# ProPrj_usb__2025-12-14-12-09-50.net
KiCad netlist of a schematic drawn in EasyEDA Pro
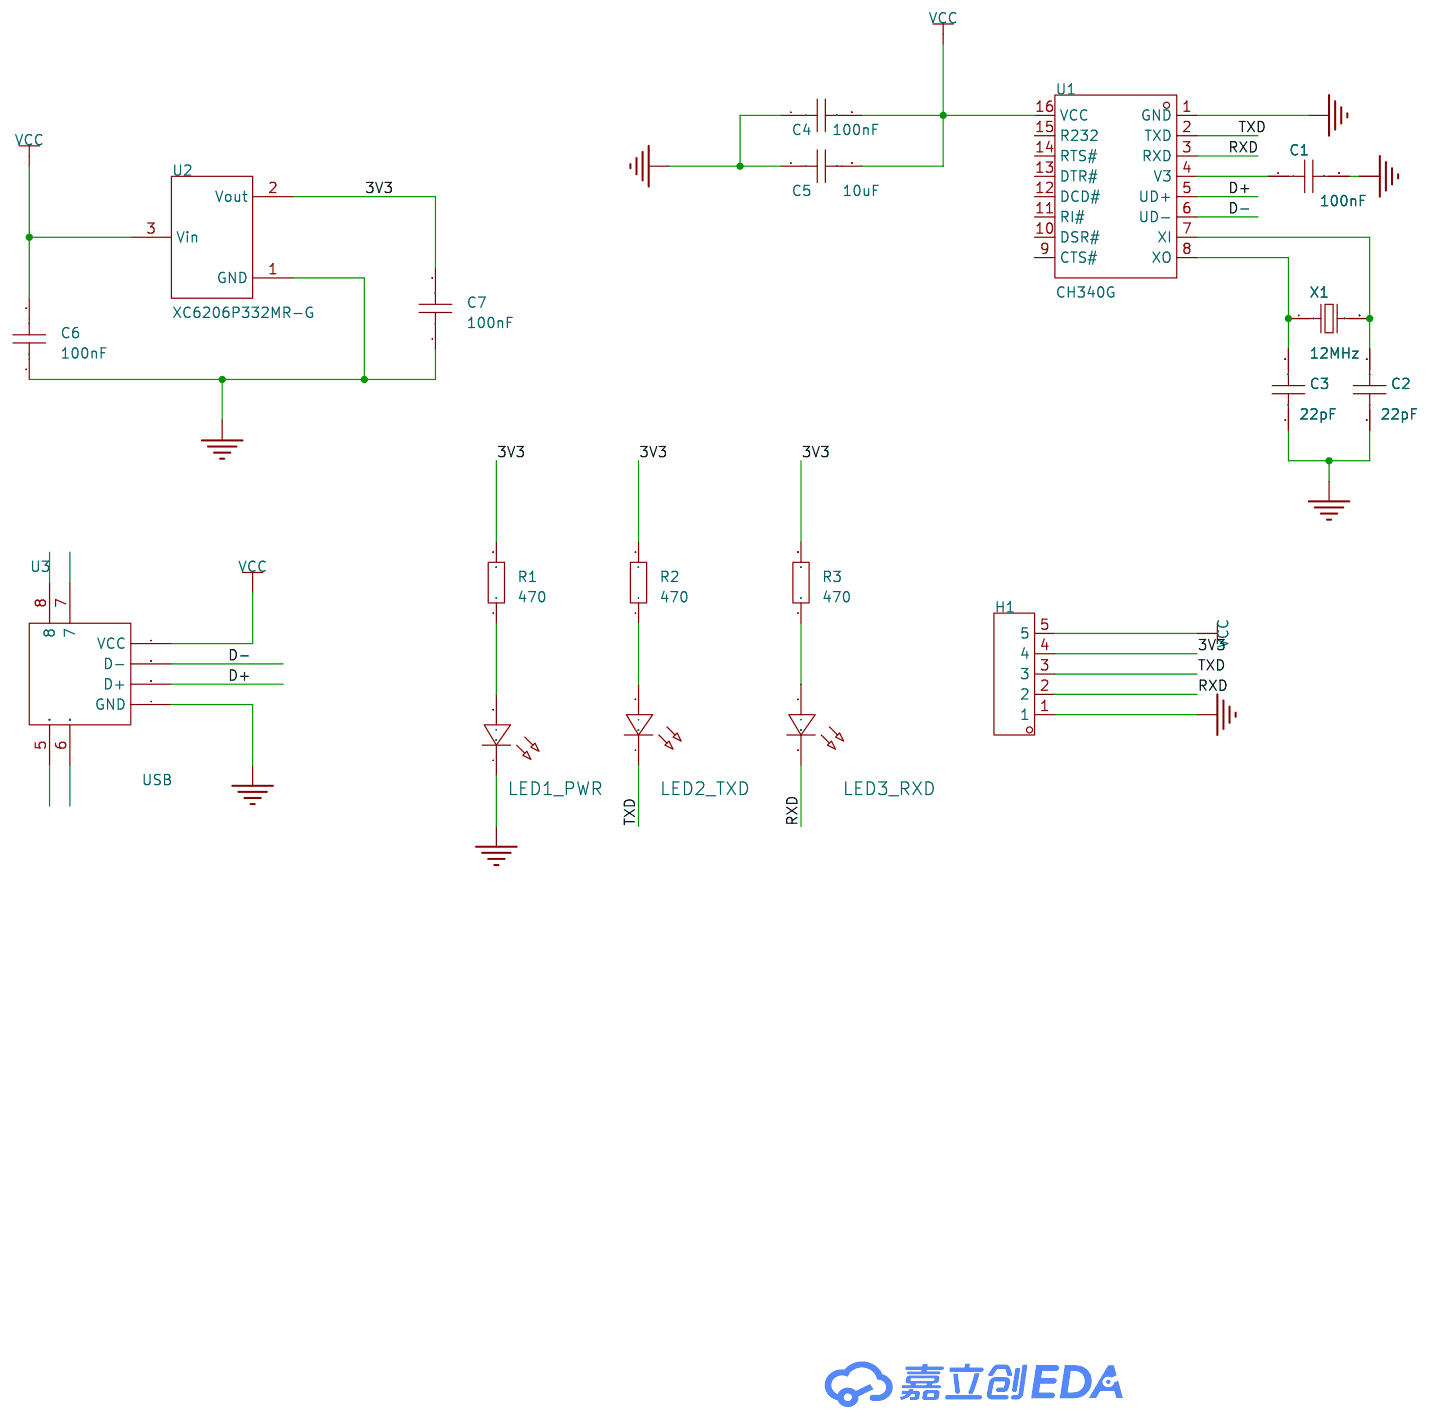
[diagram p0: schematic sheet]

(export (version "E")
  (design (tool "Eeschema 10.0.6"))
  (components
    (comp (ref "C1")
      (value "100nF")
      (footprint "easyedapro:C0603")
      (libsource (lib "easyedapro") (part "Capacitance"))
    )
    (comp (ref "C2")
      (value "22pF")
      (footprint "easyedapro:C0603")
      (libsource (lib "easyedapro") (part "Capacitance"))
    )
    (comp (ref "C3")
      (value "22pF")
      (footprint "easyedapro:C0603")
      (libsource (lib "easyedapro") (part "Capacitance"))
    )
    (comp (ref "C4")
      (value "100nF")
      (footprint "easyedapro:C0603")
      (libsource (lib "easyedapro") (part "Capacitance"))
    )
    (comp (ref "C5")
      (value "10uF")
      (footprint "easyedapro:C0603")
      (libsource (lib "easyedapro") (part "Capacitance"))
    )
    (comp (ref "C6")
      (value "100nF")
      (footprint "easyedapro:C0603")
      (libsource (lib "easyedapro") (part "Capacitance"))
    )
    (comp (ref "C7")
      (value "100nF")
      (footprint "easyedapro:C0603")
      (libsource (lib "easyedapro") (part "Capacitance"))
    )
    (comp (ref "H1")
      (value "~")
      (footprint "easyedapro:HDR-TH_5P-P2.54-V-M")
      (libsource (lib "easyedapro") (part "MTP125-1105S1"))
    )
    (comp (ref "LED1_PWR")
      (value "~")
      (footprint "easyedapro:LED_0603")
      (libsource (lib "easyedapro") (part "LED_R"))
    )
    (comp (ref "LED2_TXD")
      (value "~")
      (footprint "easyedapro:LED_0603")
      (libsource (lib "easyedapro") (part "LED_R"))
    )
    (comp (ref "LED3_RXD")
      (value "~")
      (footprint "easyedapro:LED_0603")
      (libsource (lib "easyedapro") (part "LED_R"))
    )
    (comp (ref "R1") (value "470") (footprint "easyedapro:R0603") (libsource (lib "easyedapro") (part "电阻")))
    (comp (ref "R2") (value "470") (footprint "easyedapro:R0603") (libsource (lib "easyedapro") (part "电阻")))
    (comp (ref "R3") (value "470") (footprint "easyedapro:R0603") (libsource (lib "easyedapro") (part "电阻")))
    (comp (ref "U1")
      (value "CH340G")
      (footprint "easyedapro:SOIC-16_L9.9-W3.9-P1.27-LS6.0-BL")
      (description "应用功能:USB转UART;接口协议:USB 2.0;数据速率:2Mbps;")
      (fields (field (name "Manufacturer") "WCH(南京沁恒)"))
      (libsource (lib "easyedapro") (part "CH340G"))
    )
    (comp (ref "U2")
      (value "XC6206P332MR-G")
      (footprint "easyedapro:SOT-23-3_L2.9-W1.6-P1.90-LS2.8-BR")
      (description "输出类型:固定;工作电压:6V;输出电压:3.3V;输出电流:200mA;电源纹波抑制比(PSRR):-;输出极性:正极;")
      (fields (field (name "Manufacturer") "TOREX(特瑞仕)"))
      (libsource (lib "easyedapro") (part "XC6206P332MR"))
    )
    (comp (ref "U3")
      (value "USB")
      (footprint "easyedapro:USB-SMD_USB_1")
      (libsource (lib "easyedapro") (part "USB"))
    )
    (comp (ref "X1")
      (value "12MHz")
      (footprint "easyedapro:CRYSTAL-SMD_L5.0-W3.2")
      (description "晶振类型:贴片晶振;频率:12MHz;常温频差:±20ppm;负载电容:20pF;频率稳定度:±30ppm;")
      (fields
        (field (name "Manufacturer Part") "XC53G2-12.000-F20LJDT")
        (field (name "Manufacturer") "HCI(杭晶)")
      )
      (libsource (lib "easyedapro") (part "XC53G2-12.000-F20LJDT"))
    )
  )
  (nets
    (net (code "1") (name "/3V3") (class "Default")
      (node (ref "C7") (pin "2") (pinfunction "2_2") (pintype "input"))
      (node (ref "H1") (pin "4") (pinfunction "4_4") (pintype "unspecified"))
      (node (ref "R1") (pin "2") (pinfunction "2_2") (pintype "input"))
      (node (ref "R2") (pin "2") (pinfunction "2_2") (pintype "input"))
      (node (ref "R3") (pin "2") (pinfunction "2_2") (pintype "input"))
      (node (ref "U2") (pin "2") (pinfunction "Vout_2") (pintype "unspecified"))
    )
    (net (code "2") (name "/D+") (class "Default")
      (node (ref "U1") (pin "5") (pinfunction "UD+_5") (pintype "unspecified"))
      (node (ref "U3") (pin "3") (pinfunction "D+_3") (pintype "input"))
    )
    (net (code "3") (name "/D-") (class "Default")
      (node (ref "U1") (pin "6") (pinfunction "UD-_6") (pintype "unspecified"))
      (node (ref "U3") (pin "2") (pinfunction "D-_2") (pintype "input"))
    )
    (net (code "4") (name "/RXD") (class "Default")
      (node (ref "H1") (pin "2") (pinfunction "2_2") (pintype "unspecified"))
      (node (ref "LED3_RXD") (pin "1") (pinfunction "C_1") (pintype "input"))
      (node (ref "U1") (pin "3") (pinfunction "RXD_3") (pintype "unspecified"))
    )
    (net (code "5") (name "/TXD") (class "Default")
      (node (ref "H1") (pin "3") (pinfunction "3_3") (pintype "unspecified"))
      (node (ref "LED2_TXD") (pin "1") (pinfunction "C_1") (pintype "input"))
      (node (ref "U1") (pin "2") (pinfunction "TXD_2") (pintype "unspecified"))
    )
    (net (code "6") (name "GND") (class "Default")
      (node (ref "C1") (pin "2") (pinfunction "2_2") (pintype "input"))
      (node (ref "C2") (pin "1") (pinfunction "1_1") (pintype "input"))
      (node (ref "C3") (pin "1") (pinfunction "1_1") (pintype "input"))
      (node (ref "C4") (pin "1") (pinfunction "1_1") (pintype "input"))
      (node (ref "C5") (pin "1") (pinfunction "1_1") (pintype "input"))
      (node (ref "C6") (pin "1") (pinfunction "1_1") (pintype "input"))
      (node (ref "C7") (pin "1") (pinfunction "1_1") (pintype "input"))
      (node (ref "H1") (pin "1") (pinfunction "1_1") (pintype "unspecified"))
      (node (ref "LED1_PWR") (pin "1") (pinfunction "C_1") (pintype "input"))
      (node (ref "U1") (pin "1") (pinfunction "GND_1") (pintype "unspecified"))
      (node (ref "U2") (pin "1") (pinfunction "GND_1") (pintype "unspecified"))
      (node (ref "U3") (pin "4") (pinfunction "GND_4") (pintype "input"))
    )
    (net (code "7") (name "Net-(LED1_PWR-A)") (class "Default")
      (node (ref "LED1_PWR") (pin "2") (pinfunction "A_2") (pintype "input"))
      (node (ref "R1") (pin "1") (pinfunction "1_1") (pintype "input"))
    )
    (net (code "8") (name "Net-(LED2_TXD-A)") (class "Default")
      (node (ref "LED2_TXD") (pin "2") (pinfunction "A_2") (pintype "input"))
      (node (ref "R2") (pin "1") (pinfunction "1_1") (pintype "input"))
    )
    (net (code "9") (name "Net-(LED3_RXD-A)") (class "Default")
      (node (ref "LED3_RXD") (pin "2") (pinfunction "A_2") (pintype "input"))
      (node (ref "R3") (pin "1") (pinfunction "1_1") (pintype "input"))
    )
    (net (code "10") (name "Net-(U1-V3)") (class "Default")
      (node (ref "C1") (pin "1") (pinfunction "1_1") (pintype "input"))
      (node (ref "U1") (pin "4") (pinfunction "V3_4") (pintype "unspecified"))
    )
    (net (code "11") (name "Net-(U1-XI)") (class "Default")
      (node (ref "C2") (pin "2") (pinfunction "2_2") (pintype "input"))
      (node (ref "U1") (pin "7") (pinfunction "XI_7") (pintype "unspecified"))
      (node (ref "X1") (pin "2") (pinfunction "2_2") (pintype "unspecified"))
    )
    (net (code "12") (name "Net-(U1-XO)") (class "Default")
      (node (ref "C3") (pin "2") (pinfunction "2_2") (pintype "input"))
      (node (ref "U1") (pin "8") (pinfunction "XO_8") (pintype "unspecified"))
      (node (ref "X1") (pin "1") (pinfunction "1_1") (pintype "unspecified"))
    )
    (net (code "13") (name "VCC") (class "Default")
      (node (ref "C4") (pin "2") (pinfunction "2_2") (pintype "input"))
      (node (ref "C5") (pin "2") (pinfunction "2_2") (pintype "input"))
      (node (ref "C6") (pin "2") (pinfunction "2_2") (pintype "input"))
      (node (ref "H1") (pin "5") (pinfunction "5_5") (pintype "unspecified"))
      (node (ref "U1") (pin "16") (pinfunction "VCC_16") (pintype "unspecified"))
      (node (ref "U2") (pin "3") (pinfunction "Vin_3") (pintype "unspecified"))
      (node (ref "U3") (pin "1") (pinfunction "VCC_1") (pintype "input"))
    )
    (net (code "14") (name "unconnected-(U1-CTS#-Pad9)") (class "Default")
      (node (ref "U1") (pin "9") (pinfunction "CTS#_9") (pintype "unspecified"))
    )
    (net (code "15") (name "unconnected-(U1-DCD#-Pad12)") (class "Default")
      (node (ref "U1") (pin "12") (pinfunction "DCD#_12") (pintype "unspecified"))
    )
    (net (code "16") (name "unconnected-(U1-DSR#-Pad10)") (class "Default")
      (node (ref "U1") (pin "10") (pinfunction "DSR#_10") (pintype "unspecified"))
    )
    (net (code "17") (name "unconnected-(U1-DTR#-Pad13)") (class "Default")
      (node (ref "U1") (pin "13") (pinfunction "DTR#_13") (pintype "unspecified"))
    )
    (net (code "18") (name "unconnected-(U1-R232-Pad15)") (class "Default")
      (node (ref "U1") (pin "15") (pinfunction "R232_15") (pintype "unspecified"))
    )
    (net (code "19") (name "unconnected-(U1-RI#-Pad11)") (class "Default")
      (node (ref "U1") (pin "11") (pinfunction "RI#_11") (pintype "unspecified"))
    )
    (net (code "20") (name "unconnected-(U1-RTS#-Pad14)") (class "Default")
      (node (ref "U1") (pin "14") (pinfunction "RTS#_14") (pintype "unspecified"))
    )
    (net (code "21") (name "unconnected-(U3-Pad7)") (class "Default")
      (node (ref "U3") (pin "7") (pinfunction "7_7") (pintype "unspecified"))
    )
    (net (code "22") (name "unconnected-(U3-Pad8)") (class "Default")
      (node (ref "U3") (pin "8") (pinfunction "8_8") (pintype "unspecified"))
    )
    (net (code "23") (name "unconnected-(U3-SH1-Pad5)") (class "Default")
      (node (ref "U3") (pin "5") (pinfunction "SH1_5") (pintype "unspecified"))
    )
    (net (code "24") (name "unconnected-(U3-SH2-Pad6)") (class "Default")
      (node (ref "U3") (pin "6") (pinfunction "SH2_6") (pintype "unspecified"))
    )
  )
)
